# 380_NFB.net
KiCad netlist of a schematic drawn in EAGLE
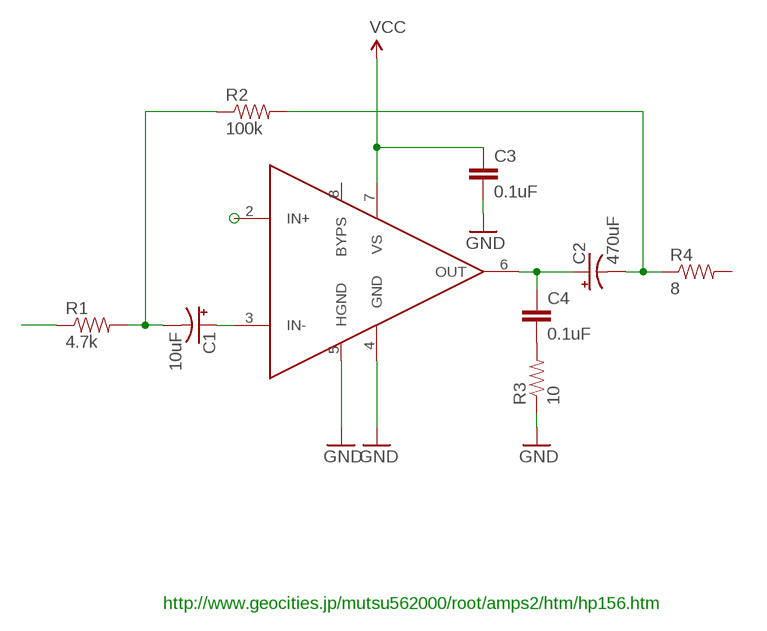
[diagram p0: schematic, sheet 1]

(export (version "E")
  (design (tool "Eeschema 10.0.6"))
  (components
    (comp (ref "C1")
      (value "10uF")
      (footprint "eagle-import:CPOL-RADIAL-100UF-25V")
      (libsource (lib "eagle-import") (part "CAP_POLPTH1"))
    )
    (comp (ref "C2")
      (value "470uF")
      (footprint "eagle-import:CPOL-RADIAL-1000UF-25V")
      (libsource (lib "eagle-import") (part "CAP_POLPTH4"))
    )
    (comp (ref "C3")
      (value "0.1uF")
      (footprint "eagle-import:CAP-PTH-SMALL-KIT")
      (libsource (lib "eagle-import") (part "CAPKIT"))
    )
    (comp (ref "C4")
      (value "0.1uF")
      (footprint "eagle-import:CAP-PTH-SMALL-KIT")
      (libsource (lib "eagle-import") (part "CAPKIT"))
    )
    (comp (ref "R1")
      (value "4.7k")
      (footprint "eagle-import:AXIAL-0.3")
      (libsource (lib "eagle-import") (part "RESISTORAXIAL-0.3"))
    )
    (comp (ref "R2")
      (value "100k")
      (footprint "eagle-import:AXIAL-0.3")
      (libsource (lib "eagle-import") (part "RESISTORAXIAL-0.3"))
    )
    (comp (ref "R3")
      (value "10")
      (footprint "eagle-import:AXIAL-0.3")
      (libsource (lib "eagle-import") (part "RESISTORAXIAL-0.3"))
    )
    (comp (ref "R4")
      (value "8")
      (footprint "eagle-import:AXIAL-0.3")
      (libsource (lib "eagle-import") (part "RESISTORAXIAL-0.3"))
    )
    (comp (ref "U$1")
      (value "LM380N-8")
      (footprint "eagle-import:DIL08")
      (libsource (lib "eagle-import") (part "LM380N-8"))
    )
  )
  (nets
    (net (code "1") (name "GND") (class "Default")
      (node (ref "C3") (pin "2") (pinfunction "2_2") (pintype "passive"))
      (node (ref "R3") (pin "P$1") (pinfunction "1_P$1") (pintype "passive"))
      (node (ref "U$1") (pin "4") (pinfunction "GND_4") (pintype "power_in"))
      (node (ref "U$1") (pin "5") (pinfunction "HGND_5") (pintype "power_in"))
    )
    (net (code "2") (name "Net-(C1-+)") (class "Default")
      (node (ref "C1") (pin "1") (pinfunction "+_1") (pintype "passive"))
      (node (ref "U$1") (pin "3") (pinfunction "IN-_3") (pintype "bidirectional"))
    )
    (net (code "3") (name "Net-(C1--)") (class "Default")
      (node (ref "C1") (pin "2") (pinfunction "-_2") (pintype "passive"))
      (node (ref "R1") (pin "P$2") (pinfunction "2_P$2") (pintype "passive"))
      (node (ref "R2") (pin "P$1") (pinfunction "1_P$1") (pintype "passive"))
    )
    (net (code "4") (name "Net-(C2-+)") (class "Default")
      (node (ref "C2") (pin "1") (pinfunction "+_1") (pintype "passive"))
      (node (ref "C4") (pin "1") (pinfunction "1_1") (pintype "passive"))
      (node (ref "U$1") (pin "6") (pinfunction "OUT_6") (pintype "output"))
    )
    (net (code "5") (name "Net-(C2--)") (class "Default")
      (node (ref "C2") (pin "2") (pinfunction "-_2") (pintype "passive"))
      (node (ref "R2") (pin "P$2") (pinfunction "2_P$2") (pintype "passive"))
      (node (ref "R4") (pin "P$1") (pinfunction "1_P$1") (pintype "passive"))
    )
    (net (code "6") (name "Net-(R3-2)") (class "Default")
      (node (ref "C4") (pin "2") (pinfunction "2_2") (pintype "passive"))
      (node (ref "R3") (pin "P$2") (pinfunction "2_P$2") (pintype "passive"))
    )
    (net (code "7") (name "VCC") (class "Default")
      (node (ref "C3") (pin "1") (pinfunction "1_1") (pintype "passive"))
      (node (ref "U$1") (pin "7") (pinfunction "VS_7") (pintype "power_in"))
    )
    (net (code "8") (name "unconnected-(R1-1-PadP$1)") (class "Default")
      (node (ref "R1") (pin "P$1") (pinfunction "1_P$1") (pintype "passive"))
    )
    (net (code "9") (name "unconnected-(R4-2-PadP$2)") (class "Default")
      (node (ref "R4") (pin "P$2") (pinfunction "2_P$2") (pintype "passive"))
    )
    (net (code "10") (name "unconnected-(U$1-BYPS-Pad8)") (class "Default")
      (node (ref "U$1") (pin "8") (pinfunction "BYPS_8") (pintype "passive"))
    )
    (net (code "11") (name "unconnected-(U$1-IN+-Pad2)") (class "Default")
      (node (ref "U$1") (pin "2") (pinfunction "IN+_2") (pintype "input"))
    )
  )
)
